# lm3410-sepic-led-driver-20mm-mk1.net
KiCad netlist of a schematic drawn in EAGLE
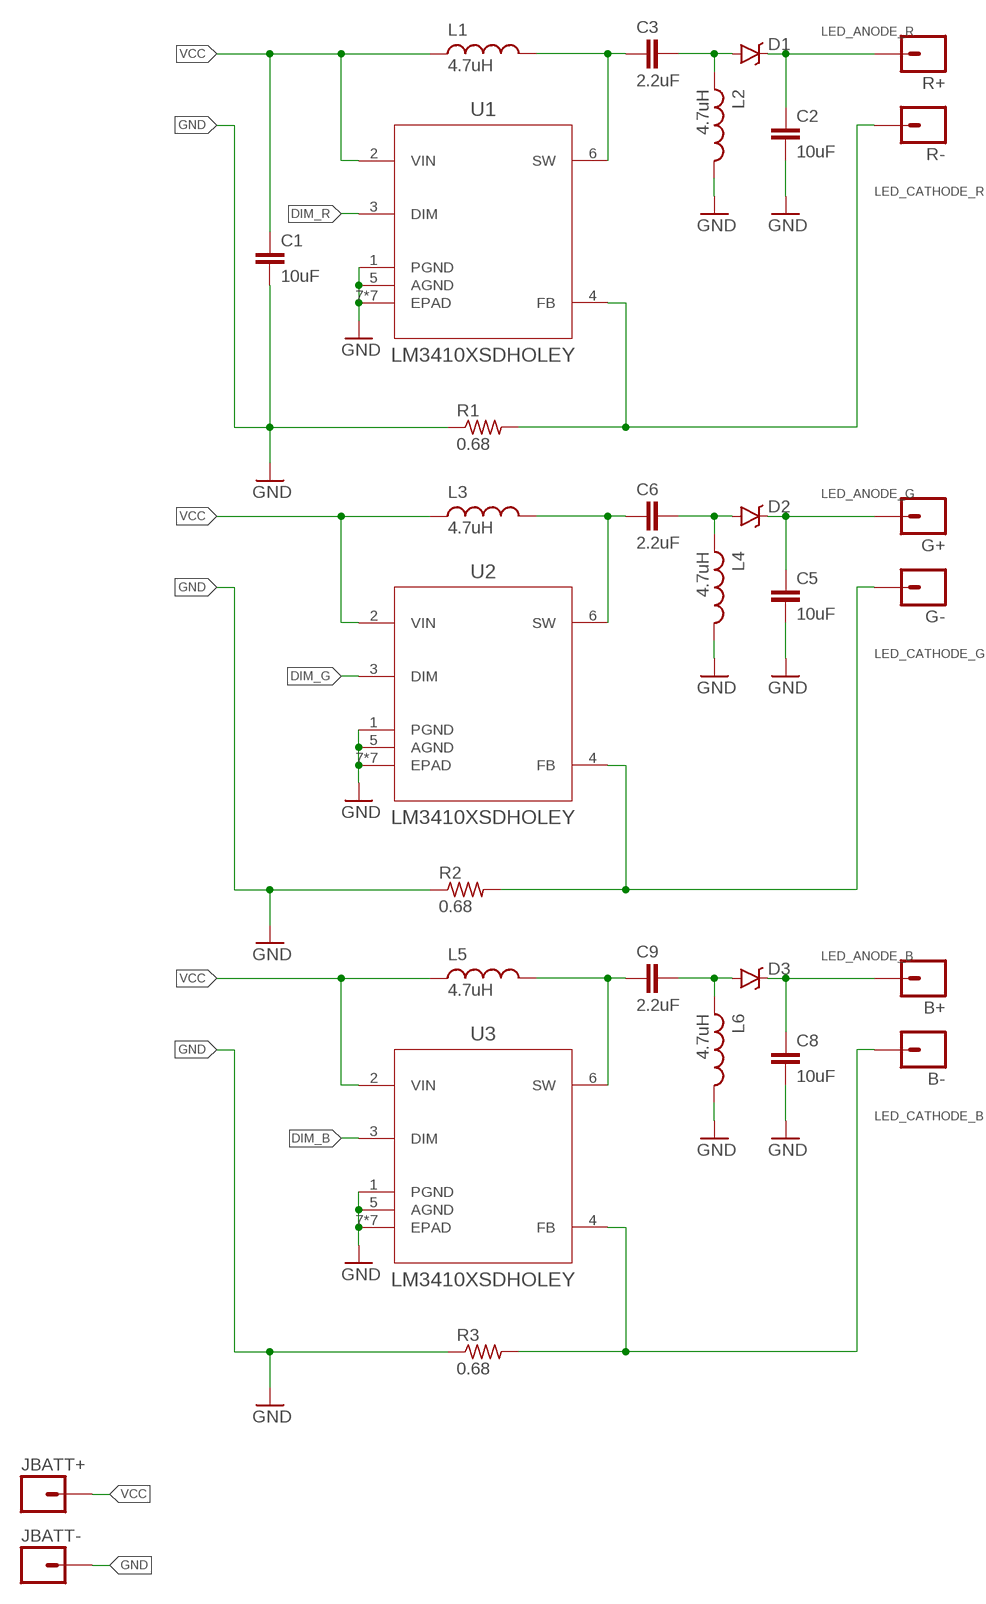
[diagram p0: schematic, sheet 1]

(export (version "E")
  (design (tool "Eeschema 10.0.6"))
  (components
    (comp (ref "B+")
      (value "M01PTH-1.2MM")
      (footprint "eagle-import:1X01-1.2MM")
      (libsource (lib "eagle-import") (part "M01PTH-1.2MM"))
    )
    (comp (ref "B-")
      (value "M01PTH-1.2MM-NS")
      (footprint "eagle-import:1X01-1.2MM-NS")
      (libsource (lib "eagle-import") (part "M01PTH-1.2MM-NS"))
    )
    (comp (ref "C1")
      (value "10uF")
      (footprint "eagle-import:C0603")
      (libsource (lib "eagle-import") (part "CAPACITOR-CERAMICC0603"))
    )
    (comp (ref "C2")
      (value "10uF")
      (footprint "eagle-import:C0603")
      (libsource (lib "eagle-import") (part "CAPACITOR-CERAMICC0603"))
    )
    (comp (ref "C3")
      (value "2.2uF")
      (footprint "eagle-import:C0805")
      (libsource (lib "eagle-import") (part "CAPACITOR-CERAMICC0805"))
    )
    (comp (ref "C5")
      (value "10uF")
      (footprint "eagle-import:C0603")
      (libsource (lib "eagle-import") (part "CAPACITOR-CERAMICC0603"))
    )
    (comp (ref "C6")
      (value "2.2uF")
      (footprint "eagle-import:C0805")
      (libsource (lib "eagle-import") (part "CAPACITOR-CERAMICC0805"))
    )
    (comp (ref "C8")
      (value "10uF")
      (footprint "eagle-import:C0603")
      (libsource (lib "eagle-import") (part "CAPACITOR-CERAMICC0603"))
    )
    (comp (ref "C9")
      (value "2.2uF")
      (footprint "eagle-import:C0805")
      (libsource (lib "eagle-import") (part "CAPACITOR-CERAMICC0805"))
    )
    (comp (ref "D1")
      (value "PMEG4005EJ")
      (footprint "eagle-import:SOD-323")
      (libsource (lib "eagle-import") (part "DIODE-SCHOTTKY-PMEG4005EJ"))
    )
    (comp (ref "D2")
      (value "PMEG4005EJ")
      (footprint "eagle-import:SOD-323")
      (libsource (lib "eagle-import") (part "DIODE-SCHOTTKY-PMEG4005EJ"))
    )
    (comp (ref "D3")
      (value "PMEG4005EJ")
      (footprint "eagle-import:SOD-323")
      (libsource (lib "eagle-import") (part "DIODE-SCHOTTKY-PMEG4005EJ"))
    )
    (comp (ref "G+")
      (value "M01PTH-1.2MM")
      (footprint "eagle-import:1X01-1.2MM")
      (libsource (lib "eagle-import") (part "M01PTH-1.2MM"))
    )
    (comp (ref "G-")
      (value "M01PTH-1.2MM-NS")
      (footprint "eagle-import:1X01-1.2MM-NS")
      (libsource (lib "eagle-import") (part "M01PTH-1.2MM-NS"))
    )
    (comp (ref "JBATT+")
      (value "M01NOT-A-VIA-NOPE")
      (footprint "eagle-import:1X01_NOSILK_NOSTOP")
      (libsource (lib "eagle-import") (part "M01NOT-A-VIA-NOPE"))
    )
    (comp (ref "JBATT-")
      (value "M01NOT-A-VIA-NOPE")
      (footprint "eagle-import:1X01_NOSILK_NOSTOP")
      (libsource (lib "eagle-import") (part "M01NOT-A-VIA-NOPE"))
    )
    (comp (ref "L1")
      (value "4.7uH")
      (footprint "eagle-import:INDUCTOR_2X1.6MM")
      (libsource (lib "eagle-import") (part "INDUCTORIFSC-0806"))
    )
    (comp (ref "L2")
      (value "4.7uH")
      (footprint "eagle-import:INDUCTOR_2X1.6MM")
      (libsource (lib "eagle-import") (part "INDUCTORIFSC-0806"))
    )
    (comp (ref "L3")
      (value "4.7uH")
      (footprint "eagle-import:INDUCTOR_2X1.6MM")
      (libsource (lib "eagle-import") (part "INDUCTORIFSC-0806"))
    )
    (comp (ref "L4")
      (value "4.7uH")
      (footprint "eagle-import:INDUCTOR_2X1.6MM")
      (libsource (lib "eagle-import") (part "INDUCTORIFSC-0806"))
    )
    (comp (ref "L5")
      (value "4.7uH")
      (footprint "eagle-import:INDUCTOR_2X1.6MM")
      (libsource (lib "eagle-import") (part "INDUCTORIFSC-0806"))
    )
    (comp (ref "L6")
      (value "4.7uH")
      (footprint "eagle-import:INDUCTOR_2X1.6MM")
      (libsource (lib "eagle-import") (part "INDUCTORIFSC-0806"))
    )
    (comp (ref "R+")
      (value "M01PTH-1.2MM")
      (footprint "eagle-import:1X01-1.2MM")
      (libsource (lib "eagle-import") (part "M01PTH-1.2MM"))
    )
    (comp (ref "R-")
      (value "M01PTH-1.2MM-NS")
      (footprint "eagle-import:1X01-1.2MM-NS")
      (libsource (lib "eagle-import") (part "M01PTH-1.2MM-NS"))
    )
    (comp (ref "R1")
      (value "0.68")
      (footprint "eagle-import:R1206")
      (libsource (lib "eagle-import") (part "RESISTORR1206"))
    )
    (comp (ref "R2")
      (value "0.68")
      (footprint "eagle-import:R1206")
      (libsource (lib "eagle-import") (part "RESISTORR1206"))
    )
    (comp (ref "R3")
      (value "0.68")
      (footprint "eagle-import:R1206")
      (libsource (lib "eagle-import") (part "RESISTORR1206"))
    )
    (comp (ref "U1")
      (value "LM3410XSDHOLEY")
      (footprint "eagle-import:DFN300X300X80-7N-HOLES")
      (libsource (lib "eagle-import") (part "LM3410XSDHOLEY"))
    )
    (comp (ref "U2")
      (value "LM3410XSDHOLEY")
      (footprint "eagle-import:DFN300X300X80-7N-HOLES")
      (libsource (lib "eagle-import") (part "LM3410XSDHOLEY"))
    )
    (comp (ref "U3")
      (value "LM3410XSDHOLEY")
      (footprint "eagle-import:DFN300X300X80-7N-HOLES")
      (libsource (lib "eagle-import") (part "LM3410XSDHOLEY"))
    )
  )
  (nets
    (net (code "1") (name "/LED_ANODE_B") (class "Default")
      (node (ref "B+") (pin "P$1") (pinfunction "1_P$1") (pintype "passive"))
      (node (ref "C8") (pin "1") (pinfunction "1_1") (pintype "passive"))
      (node (ref "D3") (pin "C") (pinfunction "C_C") (pintype "passive"))
    )
    (net (code "2") (name "/LED_ANODE_G") (class "Default")
      (node (ref "C5") (pin "1") (pinfunction "1_1") (pintype "passive"))
      (node (ref "D2") (pin "C") (pinfunction "C_C") (pintype "passive"))
      (node (ref "G+") (pin "P$1") (pinfunction "1_P$1") (pintype "passive"))
    )
    (net (code "3") (name "/LED_ANODE_R") (class "Default")
      (node (ref "C2") (pin "1") (pinfunction "1_1") (pintype "passive"))
      (node (ref "D1") (pin "C") (pinfunction "C_C") (pintype "passive"))
      (node (ref "R+") (pin "P$1") (pinfunction "1_P$1") (pintype "passive"))
    )
    (net (code "4") (name "/LED_CATHODE_B") (class "Default")
      (node (ref "B-") (pin "P$1") (pinfunction "1_P$1") (pintype "passive"))
      (node (ref "R3") (pin "2") (pinfunction "2_2") (pintype "passive"))
      (node (ref "U3") (pin "4") (pinfunction "FB_4") (pintype "input"))
    )
    (net (code "5") (name "/LED_CATHODE_G") (class "Default")
      (node (ref "G-") (pin "P$1") (pinfunction "1_P$1") (pintype "passive"))
      (node (ref "R2") (pin "2") (pinfunction "2_2") (pintype "passive"))
      (node (ref "U2") (pin "4") (pinfunction "FB_4") (pintype "input"))
    )
    (net (code "6") (name "/LED_CATHODE_R") (class "Default")
      (node (ref "R-") (pin "P$1") (pinfunction "1_P$1") (pintype "passive"))
      (node (ref "R1") (pin "2") (pinfunction "2_2") (pintype "passive"))
      (node (ref "U1") (pin "4") (pinfunction "FB_4") (pintype "input"))
    )
    (net (code "7") (name "DIM_B") (class "Default")
      (node (ref "U3") (pin "3") (pinfunction "DIM_3") (pintype "input"))
    )
    (net (code "8") (name "DIM_G") (class "Default")
      (node (ref "U2") (pin "3") (pinfunction "DIM_3") (pintype "input"))
    )
    (net (code "9") (name "DIM_R") (class "Default")
      (node (ref "U1") (pin "3") (pinfunction "DIM_3") (pintype "input"))
    )
    (net (code "10") (name "GND") (class "Default")
      (node (ref "C1") (pin "2") (pinfunction "2_2") (pintype "passive"))
      (node (ref "C2") (pin "2") (pinfunction "2_2") (pintype "passive"))
      (node (ref "C5") (pin "2") (pinfunction "2_2") (pintype "passive"))
      (node (ref "C8") (pin "2") (pinfunction "2_2") (pintype "passive"))
      (node (ref "JBATT-") (pin "P$1") (pinfunction "1_P$1") (pintype "passive"))
      (node (ref "L2") (pin "P$2") (pinfunction "2_P$2") (pintype "passive"))
      (node (ref "L4") (pin "P$2") (pinfunction "2_P$2") (pintype "passive"))
      (node (ref "L6") (pin "P$2") (pinfunction "2_P$2") (pintype "passive"))
      (node (ref "R1") (pin "1") (pinfunction "1_1") (pintype "passive"))
      (node (ref "R2") (pin "1") (pinfunction "1_1") (pintype "passive"))
      (node (ref "R3") (pin "1") (pinfunction "1_1") (pintype "passive"))
      (node (ref "U1") (pin "1") (pinfunction "PGND_1") (pintype "passive"))
      (node (ref "U1") (pin "5") (pinfunction "AGND_5") (pintype "passive"))
      (node (ref "U1") (pin "7") (pinfunction "EPAD_7") (pintype "passive"))
      (node (ref "U1") (pin "7@1") (pinfunction "EPAD_7@1") (pintype "passive"))
      (node (ref "U1") (pin "7@2") (pinfunction "EPAD_7@2") (pintype "passive"))
      (node (ref "U1") (pin "7@3") (pinfunction "EPAD_7@3") (pintype "passive"))
      (node (ref "U1") (pin "7@4") (pinfunction "EPAD_7@4") (pintype "passive"))
      (node (ref "U1") (pin "7@5") (pinfunction "EPAD_7@5") (pintype "passive"))
      (node (ref "U1") (pin "7@6") (pinfunction "EPAD_7@6") (pintype "passive"))
      (node (ref "U2") (pin "1") (pinfunction "PGND_1") (pintype "passive"))
      (node (ref "U2") (pin "5") (pinfunction "AGND_5") (pintype "passive"))
      (node (ref "U2") (pin "7") (pinfunction "EPAD_7") (pintype "passive"))
      (node (ref "U2") (pin "7@1") (pinfunction "EPAD_7@1") (pintype "passive"))
      (node (ref "U2") (pin "7@2") (pinfunction "EPAD_7@2") (pintype "passive"))
      (node (ref "U2") (pin "7@3") (pinfunction "EPAD_7@3") (pintype "passive"))
      (node (ref "U2") (pin "7@4") (pinfunction "EPAD_7@4") (pintype "passive"))
      (node (ref "U2") (pin "7@5") (pinfunction "EPAD_7@5") (pintype "passive"))
      (node (ref "U2") (pin "7@6") (pinfunction "EPAD_7@6") (pintype "passive"))
      (node (ref "U3") (pin "1") (pinfunction "PGND_1") (pintype "passive"))
      (node (ref "U3") (pin "5") (pinfunction "AGND_5") (pintype "passive"))
      (node (ref "U3") (pin "7") (pinfunction "EPAD_7") (pintype "passive"))
      (node (ref "U3") (pin "7@1") (pinfunction "EPAD_7@1") (pintype "passive"))
      (node (ref "U3") (pin "7@2") (pinfunction "EPAD_7@2") (pintype "passive"))
      (node (ref "U3") (pin "7@3") (pinfunction "EPAD_7@3") (pintype "passive"))
      (node (ref "U3") (pin "7@4") (pinfunction "EPAD_7@4") (pintype "passive"))
      (node (ref "U3") (pin "7@5") (pinfunction "EPAD_7@5") (pintype "passive"))
      (node (ref "U3") (pin "7@6") (pinfunction "EPAD_7@6") (pintype "passive"))
    )
    (net (code "11") (name "Net-(L1-2)") (class "Default")
      (node (ref "C3") (pin "1") (pinfunction "1_1") (pintype "passive"))
      (node (ref "L1") (pin "P$2") (pinfunction "2_P$2") (pintype "passive"))
      (node (ref "U1") (pin "6") (pinfunction "SW_6") (pintype "output"))
    )
    (net (code "12") (name "Net-(L2-1)") (class "Default")
      (node (ref "C3") (pin "2") (pinfunction "2_2") (pintype "passive"))
      (node (ref "D1") (pin "A") (pinfunction "A_A") (pintype "passive"))
      (node (ref "L2") (pin "P$1") (pinfunction "1_P$1") (pintype "passive"))
    )
    (net (code "13") (name "Net-(L3-2)") (class "Default")
      (node (ref "C6") (pin "1") (pinfunction "1_1") (pintype "passive"))
      (node (ref "L3") (pin "P$2") (pinfunction "2_P$2") (pintype "passive"))
      (node (ref "U2") (pin "6") (pinfunction "SW_6") (pintype "output"))
    )
    (net (code "14") (name "Net-(L4-1)") (class "Default")
      (node (ref "C6") (pin "2") (pinfunction "2_2") (pintype "passive"))
      (node (ref "D2") (pin "A") (pinfunction "A_A") (pintype "passive"))
      (node (ref "L4") (pin "P$1") (pinfunction "1_P$1") (pintype "passive"))
    )
    (net (code "15") (name "Net-(L5-2)") (class "Default")
      (node (ref "C9") (pin "1") (pinfunction "1_1") (pintype "passive"))
      (node (ref "L5") (pin "P$2") (pinfunction "2_P$2") (pintype "passive"))
      (node (ref "U3") (pin "6") (pinfunction "SW_6") (pintype "output"))
    )
    (net (code "16") (name "Net-(L6-1)") (class "Default")
      (node (ref "C9") (pin "2") (pinfunction "2_2") (pintype "passive"))
      (node (ref "D3") (pin "A") (pinfunction "A_A") (pintype "passive"))
      (node (ref "L6") (pin "P$1") (pinfunction "1_P$1") (pintype "passive"))
    )
    (net (code "17") (name "VCC") (class "Default")
      (node (ref "C1") (pin "1") (pinfunction "1_1") (pintype "passive"))
      (node (ref "JBATT+") (pin "P$1") (pinfunction "1_P$1") (pintype "passive"))
      (node (ref "L1") (pin "P$1") (pinfunction "1_P$1") (pintype "passive"))
      (node (ref "L3") (pin "P$1") (pinfunction "1_P$1") (pintype "passive"))
      (node (ref "L5") (pin "P$1") (pinfunction "1_P$1") (pintype "passive"))
      (node (ref "U1") (pin "2") (pinfunction "VIN_2") (pintype "power_in"))
      (node (ref "U2") (pin "2") (pinfunction "VIN_2") (pintype "power_in"))
      (node (ref "U3") (pin "2") (pinfunction "VIN_2") (pintype "power_in"))
    )
  )
)
